# STM32.net
KiCad netlist of a schematic drawn in Altium Designer
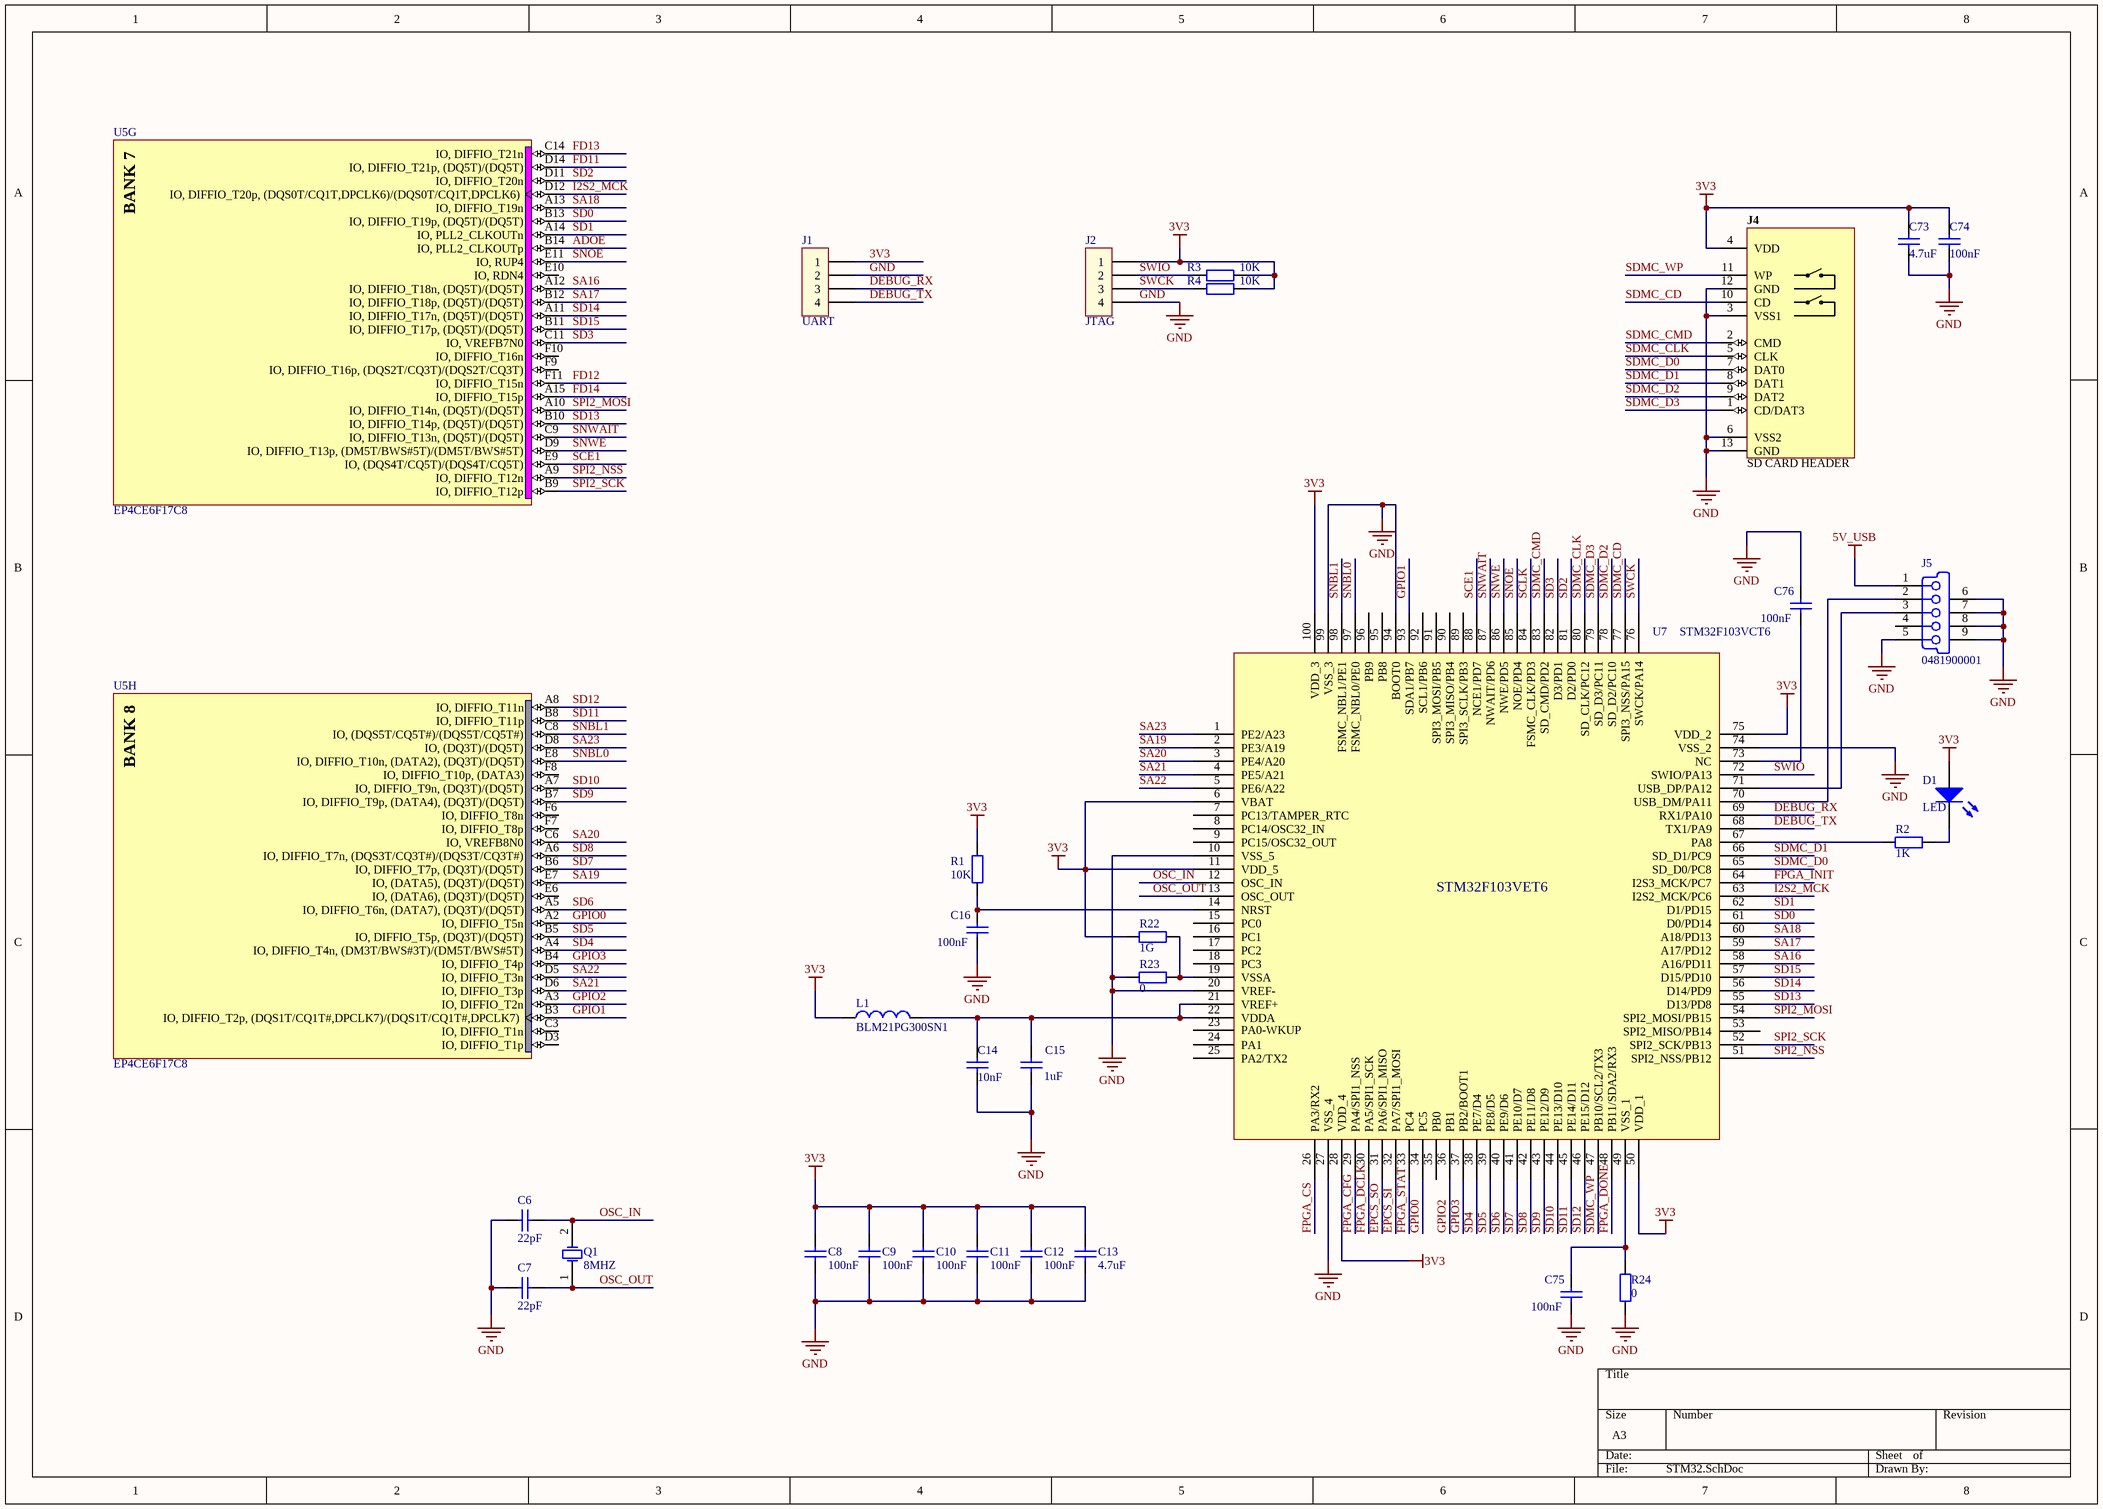
[diagram p0: STM32.SchDoc]

(export (version "E")
  (design (tool "Eeschema 10.0.6"))
  (components
    (comp (ref "C6")
      (value "22pF")
      (footprint "C0603")
      (description "Capacitor")
      (fields (field (name "PUBLISHER") "Altium Limited"))
      (libsource (lib "Miscellaneous Devices") (part "Cap"))
    )
    (comp (ref "C7")
      (value "22pF")
      (footprint "C0603")
      (description "Capacitor")
      (fields (field (name "PUBLISHER") "Altium Limited"))
      (libsource (lib "Miscellaneous Devices") (part "Cap"))
    )
    (comp (ref "C8")
      (value "100nF")
      (footprint "C0603")
      (description "Capacitor")
      (fields (field (name "PUBLISHER") "Altium Limited"))
      (libsource (lib "Miscellaneous Devices") (part "Cap"))
    )
    (comp (ref "C9")
      (value "100nF")
      (footprint "C0603")
      (description "Capacitor")
      (fields (field (name "PUBLISHER") "Altium Limited"))
      (libsource (lib "Miscellaneous Devices") (part "Cap"))
    )
    (comp (ref "C10")
      (value "100nF")
      (footprint "C0603")
      (description "Capacitor")
      (fields (field (name "PUBLISHER") "Altium Limited"))
      (libsource (lib "Miscellaneous Devices") (part "Cap"))
    )
    (comp (ref "C11")
      (value "100nF")
      (footprint "C0603")
      (description "Capacitor")
      (fields (field (name "PUBLISHER") "Altium Limited"))
      (libsource (lib "Miscellaneous Devices") (part "Cap"))
    )
    (comp (ref "C12")
      (value "100nF")
      (footprint "C0603")
      (description "Capacitor")
      (fields (field (name "PUBLISHER") "Altium Limited"))
      (libsource (lib "Miscellaneous Devices") (part "Cap"))
    )
    (comp (ref "C13")
      (value "4.7uF")
      (footprint "C0603")
      (description "Capacitor")
      (fields (field (name "PUBLISHER") "Altium Limited"))
      (libsource (lib "Miscellaneous Devices") (part "Cap"))
    )
    (comp (ref "C14")
      (value "10nF")
      (footprint "C0603")
      (description "Capacitor")
      (fields (field (name "PUBLISHER") "Altium Limited"))
      (libsource (lib "Miscellaneous Devices") (part "Cap"))
    )
    (comp (ref "C15")
      (value "1uF")
      (footprint "C0603")
      (description "Capacitor")
      (fields (field (name "PUBLISHER") "Altium Limited"))
      (libsource (lib "Miscellaneous Devices") (part "Cap"))
    )
    (comp (ref "C16")
      (value "100nF")
      (footprint "C0603")
      (description "Capacitor")
      (fields (field (name "PUBLISHER") "Altium Limited"))
      (libsource (lib "Miscellaneous Devices") (part "Cap"))
    )
    (comp (ref "C73")
      (value "4.7uF")
      (footprint "C0603")
      (description "Capacitor")
      (fields (field (name "PUBLISHER") "Altium Limited"))
      (libsource (lib "Miscellaneous Devices") (part "Cap"))
    )
    (comp (ref "C74")
      (value "100nF")
      (footprint "C0603")
      (description "Capacitor")
      (fields (field (name "PUBLISHER") "Altium Limited"))
      (libsource (lib "Miscellaneous Devices") (part "Cap"))
    )
    (comp (ref "C75")
      (value "100nF")
      (footprint "C0603")
      (description "Capacitor")
      (fields (field (name "PUBLISHER") "Altium Limited"))
      (libsource (lib "Miscellaneous Devices") (part "Cap"))
    )
    (comp (ref "C76")
      (value "100nF")
      (footprint "C0603")
      (description "Capacitor")
      (fields (field (name "PUBLISHER") "Altium Limited"))
      (libsource (lib "Miscellaneous Devices") (part "Cap"))
    )
    (comp (ref "D1")
      (value "LED")
      (footprint "D0603")
      (description "Typical RED GaAs LED")
      (fields (field (name "PUBLISHER") "Altium Limited"))
      (libsource (lib "PCB_Project1") (part "LED1"))
    )
    (comp (ref "J1") (value "UART") (footprint "SIP4") (libsource (lib "Schlib1") (part "SIP4")))
    (comp (ref "J2") (value "JTAG") (footprint "SIP4") (libsource (lib "Schlib1") (part "SIP4")))
    (comp (ref "J4")
      (value "SD CARD HEADER")
      (footprint "KSDC012551")
      (description "Secure Digital Card Socket")
      (libsource (lib "ssmaster_1") (part "KSDC012551-9"))
    )
    (comp (ref "J5")
      (value "0481900001")
      (footprint "ssmaster_1:Micro USB")
      (fields (field (name "PUBLISHER") "Altium Limited"))
      (libsource (lib "Molex Serial Bus Mini USB") (part "0481900001"))
    )
    (comp (ref "L1")
      (value "BLM21PG300SN1")
      (footprint "R0805")
      (description "Inductor")
      (fields (field (name "PUBLISHER") "Altium Limited"))
      (libsource (lib "Miscellaneous Devices") (part "Inductor"))
    )
    (comp (ref "Q1")
      (value "8MHZ")
      (footprint "SMD_CRYSTAL")
      (description "Crystal Oscillator")
      (fields (field (name "PUBLISHER") "Altium Limited"))
      (libsource (lib "Miscellaneous Devices") (part "XTAL"))
    )
    (comp (ref "R1")
      (value "10K")
      (footprint "R0603")
      (description "Resistor")
      (fields (field (name "PUBLISHER") "Altium Limited"))
      (libsource (lib "Miscellaneous Devices") (part "Res2"))
    )
    (comp (ref "R2")
      (value "1K")
      (footprint "R0603")
      (description "Resistor")
      (fields (field (name "PUBLISHER") "Altium Limited"))
      (libsource (lib "") (part "Res2_2"))
    )
    (comp (ref "R3")
      (value "10K")
      (footprint "R0603")
      (description "Resistor")
      (fields (field (name "PUBLISHER") "Altium Limited"))
      (libsource (lib "") (part "Res2_3"))
    )
    (comp (ref "R4")
      (value "10K")
      (footprint "R0603")
      (description "Resistor")
      (fields (field (name "PUBLISHER") "Altium Limited"))
      (libsource (lib "") (part "Res2_3"))
    )
    (comp (ref "R22")
      (value "1G")
      (footprint "R0603")
      (description "Resistor")
      (fields (field (name "PUBLISHER") "Altium Limited"))
      (libsource (lib "") (part "Res2_2"))
    )
    (comp (ref "R23")
      (value "0")
      (footprint "R0603")
      (description "Resistor")
      (fields (field (name "PUBLISHER") "Altium Limited"))
      (libsource (lib "") (part "Res2_2"))
    )
    (comp (ref "R24")
      (value "0")
      (footprint "R0603")
      (description "Resistor")
      (fields (field (name "PUBLISHER") "Altium Limited"))
      (libsource (lib "") (part "Res2_1"))
    )
    (comp (ref "U5")
      (value "EP4CE6F17C8")
      (footprint "FBGA256")
      (fields (field (name "PUBLISHER") "Altium Limited"))
      (libsource (lib "Altera Cyclone IV E") (part "EP4CE6F17C8"))
    )
    (comp (ref "U7")
      (value "STM32F103VCT6")
      (footprint "TQFP-100")
      (libsource (lib "ssmaster_1") (part "STM32F103VCT6"))
    )
  )
  (nets
    (net (code "1") (name "/ADOE") (class "Default")
      (node (ref "U5") (pin "B14") (pinfunction "IO,_PLL2_CLKOUTp_B14") (pintype "bidirectional"))
    )
    (net (code "2") (name "/DEBUG_RX") (class "Default")
      (node (ref "J1") (pin "3") (pinfunction "3_3") (pintype "passive"))
      (node (ref "U7") (pin "69") (pinfunction "RX1/PA10_69") (pintype "passive"))
    )
    (net (code "3") (name "/DEBUG_TX") (class "Default")
      (node (ref "J1") (pin "4") (pinfunction "4_4") (pintype "passive"))
      (node (ref "U7") (pin "68") (pinfunction "TX1/PA9_68") (pintype "passive"))
    )
    (net (code "4") (name "/EPCS_SI") (class "Default")
      (node (ref "U7") (pin "32") (pinfunction "PA7/SPI1_MOSI_32") (pintype "passive"))
    )
    (net (code "5") (name "/EPCS_SO") (class "Default")
      (node (ref "U7") (pin "31") (pinfunction "PA6/SPI1_MISO_31") (pintype "passive"))
    )
    (net (code "6") (name "/FD11") (class "Default")
      (node (ref "U5") (pin "D14") (pinfunction "IO,_DIFFIO_T21p,_(DQ5T)/(DQ5T)_D14") (pintype "bidirectional"))
    )
    (net (code "7") (name "/FD12") (class "Default")
      (node (ref "U5") (pin "F11") (pinfunction "IO,_DIFFIO_T15n_F11") (pintype "bidirectional"))
    )
    (net (code "8") (name "/FD13") (class "Default")
      (node (ref "U5") (pin "C14") (pinfunction "IO,_DIFFIO_T21n_C14") (pintype "bidirectional"))
    )
    (net (code "9") (name "/FD14") (class "Default")
      (node (ref "U5") (pin "A15") (pinfunction "IO,_DIFFIO_T15p_A15") (pintype "bidirectional"))
    )
    (net (code "10") (name "/FPGA_CFG") (class "Default")
      (node (ref "U7") (pin "29") (pinfunction "PA4/SPI1_NSS_29") (pintype "passive"))
    )
    (net (code "11") (name "/FPGA_CS") (class "Default")
      (node (ref "U7") (pin "26") (pinfunction "PA3/RX2_26") (pintype "passive"))
    )
    (net (code "12") (name "/FPGA_DCLK") (class "Default")
      (node (ref "U7") (pin "30") (pinfunction "PA5/SPI1_SCK_30") (pintype "passive"))
    )
    (net (code "13") (name "/FPGA_DONE") (class "Default")
      (node (ref "U7") (pin "48") (pinfunction "PB11/SDA2/RX3_48") (pintype "passive"))
    )
    (net (code "14") (name "/FPGA_INIT") (class "Default")
      (node (ref "U7") (pin "64") (pinfunction "I2S3_MCK/PC7_64") (pintype "passive"))
    )
    (net (code "15") (name "/FPGA_STAT") (class "Default")
      (node (ref "U7") (pin "33") (pinfunction "PC4_33") (pintype "passive"))
    )
    (net (code "16") (name "/GPIO0") (class "Default")
      (node (ref "U5") (pin "A2") (pinfunction "IO,_DIFFIO_T5n_A2") (pintype "bidirectional"))
      (node (ref "U7") (pin "34") (pinfunction "PC5_34") (pintype "passive"))
    )
    (net (code "17") (name "/GPIO1") (class "Default")
      (node (ref "U5") (pin "B3") (pinfunction "IO,_DIFFIO_T2p,_(DQS1T/CQ1T#,DPCLK7)/(DQS1T/CQ1T#,DPCLK7)_B3") (pintype "bidirectional"))
      (node (ref "U7") (pin "93") (pinfunction "SDA1/PB7_93") (pintype "passive"))
    )
    (net (code "18") (name "/GPIO2") (class "Default")
      (node (ref "U5") (pin "A3") (pinfunction "IO,_DIFFIO_T2n_A3") (pintype "bidirectional"))
      (node (ref "U7") (pin "36") (pinfunction "PB1_36") (pintype "passive"))
    )
    (net (code "19") (name "/GPIO3") (class "Default")
      (node (ref "U5") (pin "B4") (pinfunction "IO,_DIFFIO_T4p_B4") (pintype "bidirectional"))
      (node (ref "U7") (pin "37") (pinfunction "PB2/BOOT1_37") (pintype "passive"))
    )
    (net (code "20") (name "/I2S2_MCK") (class "Default")
      (node (ref "U5") (pin "D12") (pinfunction "IO,_DIFFIO_T20p,_(DQS0T/CQ1T,DPCLK6)/(DQS0T/CQ1T,DPCLK6)_D12") (pintype "bidirectional"))
      (node (ref "U7") (pin "63") (pinfunction "I2S2_MCK/PC6_63") (pintype "passive"))
    )
    (net (code "21") (name "/OSC_IN") (class "Default")
      (node (ref "C6") (pin "1") (pinfunction "1_1") (pintype "passive"))
      (node (ref "Q1") (pin "2") (pinfunction "OSC2_2") (pintype "passive"))
      (node (ref "U7") (pin "12") (pinfunction "OSC_IN_12") (pintype "passive"))
    )
    (net (code "22") (name "/OSC_OUT") (class "Default")
      (node (ref "C7") (pin "1") (pinfunction "1_1") (pintype "passive"))
      (node (ref "Q1") (pin "1") (pinfunction "OSC1_1") (pintype "passive"))
      (node (ref "U7") (pin "13") (pinfunction "OSC_OUT_13") (pintype "passive"))
    )
    (net (code "23") (name "/SA16") (class "Default")
      (node (ref "U5") (pin "A12") (pinfunction "IO,_DIFFIO_T18n,_(DQ5T)/(DQ5T)_A12") (pintype "bidirectional"))
      (node (ref "U7") (pin "58") (pinfunction "A16/PD11_58") (pintype "passive"))
    )
    (net (code "24") (name "/SA17") (class "Default")
      (node (ref "U5") (pin "B12") (pinfunction "IO,_DIFFIO_T18p,_(DQ5T)/(DQ5T)_B12") (pintype "bidirectional"))
      (node (ref "U7") (pin "59") (pinfunction "A17/PD12_59") (pintype "passive"))
    )
    (net (code "25") (name "/SA18") (class "Default")
      (node (ref "U5") (pin "A13") (pinfunction "IO,_DIFFIO_T19n_A13") (pintype "bidirectional"))
      (node (ref "U7") (pin "60") (pinfunction "A18/PD13_60") (pintype "passive"))
    )
    (net (code "26") (name "/SA19") (class "Default")
      (node (ref "U5") (pin "E7") (pinfunction "IO,_(DATA5),_(DQ3T)/(DQ5T)_E7") (pintype "bidirectional"))
      (node (ref "U7") (pin "2") (pinfunction "PE3/A19_2") (pintype "passive"))
    )
    (net (code "27") (name "/SA20") (class "Default")
      (node (ref "U5") (pin "C6") (pinfunction "IO,_VREFB8N0_C6") (pintype "bidirectional"))
      (node (ref "U7") (pin "3") (pinfunction "PE4/A20_3") (pintype "passive"))
    )
    (net (code "28") (name "/SA21") (class "Default")
      (node (ref "U5") (pin "D6") (pinfunction "IO,_DIFFIO_T3p_D6") (pintype "bidirectional"))
      (node (ref "U7") (pin "4") (pinfunction "PE5/A21_4") (pintype "passive"))
    )
    (net (code "29") (name "/SA22") (class "Default")
      (node (ref "U5") (pin "D5") (pinfunction "IO,_DIFFIO_T3n_D5") (pintype "bidirectional"))
      (node (ref "U7") (pin "5") (pinfunction "PE6/A22_5") (pintype "passive"))
    )
    (net (code "30") (name "/SA23") (class "Default")
      (node (ref "U5") (pin "D8") (pinfunction "IO,_(DQ3T)/(DQ5T)_D8") (pintype "bidirectional"))
      (node (ref "U7") (pin "1") (pinfunction "PE2/A23_1") (pintype "passive"))
    )
    (net (code "31") (name "/SCE1") (class "Default")
      (node (ref "U5") (pin "E9") (pinfunction "IO,_(DQS4T/CQ5T)/(DQS4T/CQ5T)_E9") (pintype "bidirectional"))
      (node (ref "U7") (pin "88") (pinfunction "NCE1/PD7_88") (pintype "passive"))
    )
    (net (code "32") (name "/SCLK") (class "Default")
      (node (ref "U7") (pin "84") (pinfunction "FSMC_CLK/PD3_84") (pintype "passive"))
    )
    (net (code "33") (name "/SD0") (class "Default")
      (node (ref "U5") (pin "B13") (pinfunction "IO,_DIFFIO_T19p,_(DQ5T)/(DQ5T)_B13") (pintype "bidirectional"))
      (node (ref "U7") (pin "61") (pinfunction "D0/PD14_61") (pintype "passive"))
    )
    (net (code "34") (name "/SD1") (class "Default")
      (node (ref "U5") (pin "A14") (pinfunction "IO,_PLL2_CLKOUTn_A14") (pintype "bidirectional"))
      (node (ref "U7") (pin "62") (pinfunction "D1/PD15_62") (pintype "passive"))
    )
    (net (code "35") (name "/SD2") (class "Default")
      (node (ref "U5") (pin "D11") (pinfunction "IO,_DIFFIO_T20n_D11") (pintype "bidirectional"))
      (node (ref "U7") (pin "81") (pinfunction "D2/PD0_81") (pintype "passive"))
    )
    (net (code "36") (name "/SD3") (class "Default")
      (node (ref "U5") (pin "C11") (pinfunction "IO,_VREFB7N0_C11") (pintype "bidirectional"))
      (node (ref "U7") (pin "82") (pinfunction "D3/PD1_82") (pintype "passive"))
    )
    (net (code "37") (name "/SD4") (class "Default")
      (node (ref "U5") (pin "A4") (pinfunction "IO,_DIFFIO_T4n,_(DM3T/BWS#3T)/(DM5T/BWS#5T)_A4") (pintype "bidirectional"))
      (node (ref "U7") (pin "38") (pinfunction "PE7/D4_38") (pintype "passive"))
    )
    (net (code "38") (name "/SD5") (class "Default")
      (node (ref "U5") (pin "B5") (pinfunction "IO,_DIFFIO_T5p,_(DQ3T)/(DQ5T)_B5") (pintype "bidirectional"))
      (node (ref "U7") (pin "39") (pinfunction "PE8/D5_39") (pintype "passive"))
    )
    (net (code "39") (name "/SD6") (class "Default")
      (node (ref "U5") (pin "A5") (pinfunction "IO,_DIFFIO_T6n,_(DATA7),_(DQ3T)/(DQ5T)_A5") (pintype "bidirectional"))
      (node (ref "U7") (pin "40") (pinfunction "PE9/D6_40") (pintype "passive"))
    )
    (net (code "40") (name "/SD7") (class "Default")
      (node (ref "U5") (pin "B6") (pinfunction "IO,_DIFFIO_T7p,_(DQ3T)/(DQ5T)_B6") (pintype "bidirectional"))
      (node (ref "U7") (pin "41") (pinfunction "PE10/D7_41") (pintype "passive"))
    )
    (net (code "41") (name "/SD8") (class "Default")
      (node (ref "U5") (pin "A6") (pinfunction "IO,_DIFFIO_T7n,_(DQS3T/CQ3T#)/(DQS3T/CQ3T#)_A6") (pintype "bidirectional"))
      (node (ref "U7") (pin "42") (pinfunction "PE11/D8_42") (pintype "passive"))
    )
    (net (code "42") (name "/SD9") (class "Default")
      (node (ref "U5") (pin "B7") (pinfunction "IO,_DIFFIO_T9p,_(DATA4),_(DQ3T)/(DQ5T)_B7") (pintype "bidirectional"))
      (node (ref "U7") (pin "43") (pinfunction "PE12/D9_43") (pintype "passive"))
    )
    (net (code "43") (name "/SD10") (class "Default")
      (node (ref "U5") (pin "A7") (pinfunction "IO,_DIFFIO_T9n,_(DQ3T)/(DQ5T)_A7") (pintype "bidirectional"))
      (node (ref "U7") (pin "44") (pinfunction "PE13/D10_44") (pintype "passive"))
    )
    (net (code "44") (name "/SD11") (class "Default")
      (node (ref "U5") (pin "B8") (pinfunction "IO,_DIFFIO_T11p_B8") (pintype "bidirectional"))
      (node (ref "U7") (pin "45") (pinfunction "PE14/D11_45") (pintype "passive"))
    )
    (net (code "45") (name "/SD12") (class "Default")
      (node (ref "U5") (pin "A8") (pinfunction "IO,_DIFFIO_T11n_A8") (pintype "bidirectional"))
      (node (ref "U7") (pin "46") (pinfunction "PE15/D12_46") (pintype "passive"))
    )
    (net (code "46") (name "/SD13") (class "Default")
      (node (ref "U5") (pin "B10") (pinfunction "IO,_DIFFIO_T14p,_(DQ5T)/(DQ5T)_B10") (pintype "bidirectional"))
      (node (ref "U7") (pin "55") (pinfunction "D13/PD8_55") (pintype "passive"))
    )
    (net (code "47") (name "/SD14") (class "Default")
      (node (ref "U5") (pin "A11") (pinfunction "IO,_DIFFIO_T17n,_(DQ5T)/(DQ5T)_A11") (pintype "bidirectional"))
      (node (ref "U7") (pin "56") (pinfunction "D14/PD9_56") (pintype "passive"))
    )
    (net (code "48") (name "/SD15") (class "Default")
      (node (ref "U5") (pin "B11") (pinfunction "IO,_DIFFIO_T17p,_(DQ5T)/(DQ5T)_B11") (pintype "bidirectional"))
      (node (ref "U7") (pin "57") (pinfunction "D15/PD10_57") (pintype "passive"))
    )
    (net (code "49") (name "/SDMC_CD") (class "Default")
      (node (ref "J4") (pin "10") (pinfunction "CD_10") (pintype "open_collector"))
      (node (ref "U7") (pin "77") (pinfunction "SPI3_NSS/PA15_77") (pintype "passive"))
    )
    (net (code "50") (name "/SDMC_CLK") (class "Default")
      (node (ref "J4") (pin "5") (pinfunction "CLK_5") (pintype "bidirectional"))
      (node (ref "U7") (pin "80") (pinfunction "SD_CLK/PC12_80") (pintype "passive"))
    )
    (net (code "51") (name "/SDMC_CMD") (class "Default")
      (node (ref "J4") (pin "2") (pinfunction "CMD_2") (pintype "bidirectional"))
      (node (ref "U7") (pin "83") (pinfunction "SD_CMD/PD2_83") (pintype "passive"))
    )
    (net (code "52") (name "/SDMC_D0") (class "Default")
      (node (ref "J4") (pin "7") (pinfunction "DAT0_7") (pintype "bidirectional"))
      (node (ref "U7") (pin "65") (pinfunction "SD_D0/PC8_65") (pintype "passive"))
    )
    (net (code "53") (name "/SDMC_D1") (class "Default")
      (node (ref "J4") (pin "8") (pinfunction "DAT1_8") (pintype "bidirectional"))
      (node (ref "U7") (pin "66") (pinfunction "SD_D1/PC9_66") (pintype "passive"))
    )
    (net (code "54") (name "/SDMC_D2") (class "Default")
      (node (ref "J4") (pin "9") (pinfunction "DAT2_9") (pintype "bidirectional"))
      (node (ref "U7") (pin "78") (pinfunction "SD_D2/PC10_78") (pintype "passive"))
    )
    (net (code "55") (name "/SDMC_D3") (class "Default")
      (node (ref "J4") (pin "1") (pinfunction "CD/DAT3_1") (pintype "bidirectional"))
      (node (ref "U7") (pin "79") (pinfunction "SD_D3/PC11_79") (pintype "passive"))
    )
    (net (code "56") (name "/SDMC_WP") (class "Default")
      (node (ref "J4") (pin "11") (pinfunction "WP_11") (pintype "open_collector"))
      (node (ref "U7") (pin "47") (pinfunction "PB10/SCL2/TX3_47") (pintype "passive"))
    )
    (net (code "57") (name "/SNBL0") (class "Default")
      (node (ref "U5") (pin "E8") (pinfunction "IO,_DIFFIO_T10n,_(DATA2),_(DQ3T)/(DQ5T)_E8") (pintype "bidirectional"))
      (node (ref "U7") (pin "97") (pinfunction "FSMC_NBL0/PE0_97") (pintype "passive"))
    )
    (net (code "58") (name "/SNBL1") (class "Default")
      (node (ref "U5") (pin "C8") (pinfunction "IO,_(DQS5T/CQ5T#)/(DQS5T/CQ5T#)_C8") (pintype "bidirectional"))
      (node (ref "U7") (pin "98") (pinfunction "FSMC_NBL1/PE1_98") (pintype "passive"))
    )
    (net (code "59") (name "/SNOE") (class "Default")
      (node (ref "U5") (pin "E11") (pinfunction "IO,_RUP4_E11") (pintype "bidirectional"))
      (node (ref "U7") (pin "85") (pinfunction "NOE/PD4_85") (pintype "passive"))
    )
    (net (code "60") (name "/SNWAIT") (class "Default")
      (node (ref "U5") (pin "C9") (pinfunction "IO,_DIFFIO_T13n,_(DQ5T)/(DQ5T)_C9") (pintype "bidirectional"))
      (node (ref "U7") (pin "87") (pinfunction "NWAIT/PD6_87") (pintype "passive"))
    )
    (net (code "61") (name "/SNWE") (class "Default")
      (node (ref "U5") (pin "D9") (pinfunction "IO,_DIFFIO_T13p,_(DM5T/BWS#5T)/(DM5T/BWS#5T)_D9") (pintype "bidirectional"))
      (node (ref "U7") (pin "86") (pinfunction "NWE/PD5_86") (pintype "passive"))
    )
    (net (code "62") (name "/SPI2_MOSI") (class "Default")
      (node (ref "U5") (pin "A10") (pinfunction "IO,_DIFFIO_T14n,_(DQ5T)/(DQ5T)_A10") (pintype "bidirectional"))
      (node (ref "U7") (pin "54") (pinfunction "SPI2_MOSI/PB15_54") (pintype "passive"))
    )
    (net (code "63") (name "/SPI2_NSS") (class "Default")
      (node (ref "U5") (pin "A9") (pinfunction "IO,_DIFFIO_T12n_A9") (pintype "bidirectional"))
      (node (ref "U7") (pin "51") (pinfunction "SPI2_NSS/PB12_51") (pintype "passive"))
    )
    (net (code "64") (name "/SPI2_SCK") (class "Default")
      (node (ref "U5") (pin "B9") (pinfunction "IO,_DIFFIO_T12p_B9") (pintype "bidirectional"))
      (node (ref "U7") (pin "52") (pinfunction "SPI2_SCK/PB13_52") (pintype "passive"))
    )
    (net (code "65") (name "/SWCK") (class "Default")
      (node (ref "J2") (pin "3") (pinfunction "3_3") (pintype "passive"))
      (node (ref "R4") (pin "1") (pinfunction "1_1") (pintype "passive"))
      (node (ref "U7") (pin "76") (pinfunction "SWCK/PA14_76") (pintype "passive"))
    )
    (net (code "66") (name "/SWIO") (class "Default")
      (node (ref "J2") (pin "2") (pinfunction "2_2") (pintype "passive"))
      (node (ref "R3") (pin "1") (pinfunction "1_1") (pintype "passive"))
      (node (ref "U7") (pin "72") (pinfunction "SWIO/PA13_72") (pintype "passive"))
    )
    (net (code "67") (name "3V3") (class "Default")
      (node (ref "C10") (pin "2") (pinfunction "2_2") (pintype "passive"))
      (node (ref "C11") (pin "2") (pinfunction "2_2") (pintype "passive"))
      (node (ref "C12") (pin "2") (pinfunction "2_2") (pintype "passive"))
      (node (ref "C13") (pin "2") (pinfunction "2_2") (pintype "passive"))
      (node (ref "C73") (pin "2") (pinfunction "2_2") (pintype "passive"))
      (node (ref "C74") (pin "2") (pinfunction "2_2") (pintype "passive"))
      (node (ref "C8") (pin "2") (pinfunction "2_2") (pintype "passive"))
      (node (ref "C9") (pin "2") (pinfunction "2_2") (pintype "passive"))
      (node (ref "D1") (pin "1") (pinfunction "1_1") (pintype "passive"))
      (node (ref "J1") (pin "1") (pinfunction "1_1") (pintype "passive"))
      (node (ref "J2") (pin "1") (pinfunction "1_1") (pintype "passive"))
      (node (ref "J4") (pin "4") (pinfunction "VDD_4") (pintype "power_in"))
      (node (ref "L1") (pin "1") (pinfunction "1_1") (pintype "passive"))
      (node (ref "R1") (pin "2") (pinfunction "2_2") (pintype "passive"))
      (node (ref "R22") (pin "2") (pinfunction "2_2") (pintype "passive"))
      (node (ref "R3") (pin "2") (pinfunction "2_2") (pintype "passive"))
      (node (ref "R4") (pin "2") (pinfunction "2_2") (pintype "passive"))
      (node (ref "U7") (pin "100") (pinfunction "VDD_3_100") (pintype "passive"))
      (node (ref "U7") (pin "11") (pinfunction "VDD_5_11") (pintype "passive"))
      (node (ref "U7") (pin "28") (pinfunction "VDD_4_28") (pintype "passive"))
      (node (ref "U7") (pin "50") (pinfunction "VDD_1_50") (pintype "passive"))
      (node (ref "U7") (pin "6") (pinfunction "VBAT_6") (pintype "passive"))
      (node (ref "U7") (pin "75") (pinfunction "VDD_2_75") (pintype "passive"))
    )
    (net (code "68") (name "5V_USB") (class "Default")
      (node (ref "J5") (pin "1") (pinfunction "V_BUS_(5V)_1") (pintype "passive"))
    )
    (net (code "69") (name "GND") (class "Default")
      (node (ref "C10") (pin "1") (pinfunction "1_1") (pintype "passive"))
      (node (ref "C11") (pin "1") (pinfunction "1_1") (pintype "passive"))
      (node (ref "C12") (pin "1") (pinfunction "1_1") (pintype "passive"))
      (node (ref "C13") (pin "1") (pinfunction "1_1") (pintype "passive"))
      (node (ref "C14") (pin "1") (pinfunction "1_1") (pintype "passive"))
      (node (ref "C15") (pin "1") (pinfunction "1_1") (pintype "passive"))
      (node (ref "C16") (pin "2") (pinfunction "2_2") (pintype "passive"))
      (node (ref "C6") (pin "2") (pinfunction "2_2") (pintype "passive"))
      (node (ref "C7") (pin "2") (pinfunction "2_2") (pintype "passive"))
      (node (ref "C73") (pin "1") (pinfunction "1_1") (pintype "passive"))
      (node (ref "C74") (pin "1") (pinfunction "1_1") (pintype "passive"))
      (node (ref "C75") (pin "2") (pinfunction "2_2") (pintype "passive"))
      (node (ref "C76") (pin "1") (pinfunction "1_1") (pintype "passive"))
      (node (ref "C8") (pin "1") (pinfunction "1_1") (pintype "passive"))
      (node (ref "C9") (pin "1") (pinfunction "1_1") (pintype "passive"))
      (node (ref "J1") (pin "2") (pinfunction "2_2") (pintype "passive"))
      (node (ref "J2") (pin "4") (pinfunction "4_4") (pintype "passive"))
      (node (ref "J4") (pin "12") (pinfunction "GND_12") (pintype "power_in"))
      (node (ref "J4") (pin "13") (pinfunction "GND_13") (pintype "power_in"))
      (node (ref "J4") (pin "3") (pinfunction "VSS1_3") (pintype "power_in"))
      (node (ref "J4") (pin "6") (pinfunction "VSS2_6") (pintype "power_in"))
      (node (ref "J5") (pin "5") (pinfunction "GND_5") (pintype "passive"))
      (node (ref "J5") (pin "6") (pinfunction "Tab_6") (pintype "passive"))
      (node (ref "J5") (pin "7") (pinfunction "Tab_7") (pintype "passive"))
      (node (ref "J5") (pin "8") (pinfunction "Tab_8") (pintype "passive"))
      (node (ref "J5") (pin "9") (pinfunction "Tab_9") (pintype "passive"))
      (node (ref "R23") (pin "2") (pinfunction "2_2") (pintype "passive"))
      (node (ref "R24") (pin "2") (pinfunction "2_2") (pintype "passive"))
      (node (ref "U7") (pin "10") (pinfunction "VSS_5_10") (pintype "passive"))
      (node (ref "U7") (pin "20") (pinfunction "VREF-_20") (pintype "passive"))
      (node (ref "U7") (pin "27") (pinfunction "VSS_4_27") (pintype "passive"))
      (node (ref "U7") (pin "74") (pinfunction "VSS_2_74") (pintype "passive"))
      (node (ref "U7") (pin "94") (pinfunction "BOOT0_94") (pintype "passive"))
      (node (ref "U7") (pin "99") (pinfunction "VSS_3_99") (pintype "passive"))
    )
    (net (code "70") (name "Net-(D1-Pad2)") (class "Default")
      (node (ref "D1") (pin "2") (pinfunction "2_2") (pintype "passive"))
      (node (ref "R2") (pin "1") (pinfunction "1_1") (pintype "passive"))
    )
    (net (code "71") (name "Net-(J5-D+)") (class "Default")
      (node (ref "J5") (pin "3") (pinfunction "D+_3") (pintype "passive"))
      (node (ref "U7") (pin "71") (pinfunction "USB_DP/PA12_71") (pintype "passive"))
    )
    (net (code "72") (name "Net-(J5-D-)") (class "Default")
      (node (ref "J5") (pin "2") (pinfunction "D-_2") (pintype "passive"))
      (node (ref "U7") (pin "70") (pinfunction "USB_DM/PA11_70") (pintype "passive"))
    )
    (net (code "73") (name "Net-(U7-NC)") (class "Default")
      (node (ref "C76") (pin "2") (pinfunction "2_2") (pintype "passive"))
      (node (ref "U7") (pin "73") (pinfunction "NC_73") (pintype "passive"))
    )
    (net (code "74") (name "Net-(U7-NRST)") (class "Default")
      (node (ref "C16") (pin "1") (pinfunction "1_1") (pintype "passive"))
      (node (ref "R1") (pin "1") (pinfunction "1_1") (pintype "passive"))
      (node (ref "U7") (pin "14") (pinfunction "NRST_14") (pintype "passive"))
    )
    (net (code "75") (name "Net-(U7-PA8)") (class "Default")
      (node (ref "R2") (pin "2") (pinfunction "2_2") (pintype "passive"))
      (node (ref "U7") (pin "67") (pinfunction "PA8_67") (pintype "passive"))
    )
    (net (code "76") (name "Net-(U7-VDDA)") (class "Default")
      (node (ref "C14") (pin "2") (pinfunction "2_2") (pintype "passive"))
      (node (ref "C15") (pin "2") (pinfunction "2_2") (pintype "passive"))
      (node (ref "L1") (pin "2") (pinfunction "2_2") (pintype "passive"))
      (node (ref "U7") (pin "21") (pinfunction "VREF+_21") (pintype "passive"))
      (node (ref "U7") (pin "22") (pinfunction "VDDA_22") (pintype "passive"))
    )
    (net (code "77") (name "Net-(U7-VSSA)") (class "Default")
      (node (ref "R22") (pin "1") (pinfunction "1_1") (pintype "passive"))
      (node (ref "R23") (pin "1") (pinfunction "1_1") (pintype "passive"))
      (node (ref "U7") (pin "19") (pinfunction "VSSA_19") (pintype "passive"))
    )
    (net (code "78") (name "Net-(U7-VSS_1)") (class "Default")
      (node (ref "C75") (pin "1") (pinfunction "1_1") (pintype "passive"))
      (node (ref "R24") (pin "1") (pinfunction "1_1") (pintype "passive"))
      (node (ref "U7") (pin "49") (pinfunction "VSS_1_49") (pintype "passive"))
    )
    (net (code "79") (name "unconnected-(J5-NC-Pad4)") (class "Default")
      (node (ref "J5") (pin "4") (pinfunction "NC_4") (pintype "passive"))
    )
    (net (code "80") (name "unconnected-(U5G-IO,_DIFFIO_T16n-PadF10)") (class "Default")
      (node (ref "U5") (pin "F10") (pinfunction "IO,_DIFFIO_T16n_F10") (pintype "bidirectional"))
    )
    (net (code "81") (name "unconnected-(U5G-IO,_DIFFIO_T16p,_(DQS2T{slash}CQ3T){slash}(DQS2T{slash}CQ3T)-PadF9)") (class "Default")
      (node (ref "U5") (pin "F9") (pinfunction "IO,_DIFFIO_T16p,_(DQS2T/CQ3T)/(DQS2T/CQ3T)_F9") (pintype "bidirectional"))
    )
    (net (code "82") (name "unconnected-(U5G-IO,_RDN4-PadE10)") (class "Default")
      (node (ref "U5") (pin "E10") (pinfunction "IO,_RDN4_E10") (pintype "bidirectional"))
    )
    (net (code "83") (name "unconnected-(U5H-IO,_(DATA6),_(DQ3T){slash}(DQ5T)-PadE6)") (class "Default")
      (node (ref "U5") (pin "E6") (pinfunction "IO,_(DATA6),_(DQ3T)/(DQ5T)_E6") (pintype "bidirectional"))
    )
    (net (code "84") (name "unconnected-(U5H-IO,_DIFFIO_T1n-PadC3)") (class "Default")
      (node (ref "U5") (pin "C3") (pinfunction "IO,_DIFFIO_T1n_C3") (pintype "bidirectional"))
    )
    (net (code "85") (name "unconnected-(U5H-IO,_DIFFIO_T1p-PadD3)") (class "Default")
      (node (ref "U5") (pin "D3") (pinfunction "IO,_DIFFIO_T1p_D3") (pintype "bidirectional"))
    )
    (net (code "86") (name "unconnected-(U5H-IO,_DIFFIO_T8n-PadF6)") (class "Default")
      (node (ref "U5") (pin "F6") (pinfunction "IO,_DIFFIO_T8n_F6") (pintype "bidirectional"))
    )
    (net (code "87") (name "unconnected-(U5H-IO,_DIFFIO_T8p-PadF7)") (class "Default")
      (node (ref "U5") (pin "F7") (pinfunction "IO,_DIFFIO_T8p_F7") (pintype "bidirectional"))
    )
    (net (code "88") (name "unconnected-(U5H-IO,_DIFFIO_T10p,_(DATA3)-PadF8)") (class "Default")
      (node (ref "U5") (pin "F8") (pinfunction "IO,_DIFFIO_T10p,_(DATA3)_F8") (pintype "bidirectional"))
    )
    (net (code "89") (name "unconnected-(U7-PA0-WKUP-Pad23)") (class "Default")
      (node (ref "U7") (pin "23") (pinfunction "PA0-WKUP_23") (pintype "passive"))
    )
    (net (code "90") (name "unconnected-(U7-PA1-Pad24)") (class "Default")
      (node (ref "U7") (pin "24") (pinfunction "PA1_24") (pintype "passive"))
    )
    (net (code "91") (name "unconnected-(U7-PA2{slash}TX2-Pad25)") (class "Default")
      (node (ref "U7") (pin "25") (pinfunction "PA2/TX2_25") (pintype "passive"))
    )
    (net (code "92") (name "unconnected-(U7-PB0-Pad35)") (class "Default")
      (node (ref "U7") (pin "35") (pinfunction "PB0_35") (pintype "passive"))
    )
    (net (code "93") (name "unconnected-(U7-PB8-Pad95)") (class "Default")
      (node (ref "U7") (pin "95") (pinfunction "PB8_95") (pintype "passive"))
    )
    (net (code "94") (name "unconnected-(U7-PB9-Pad96)") (class "Default")
      (node (ref "U7") (pin "96") (pinfunction "PB9_96") (pintype "passive"))
    )
    (net (code "95") (name "unconnected-(U7-PC0-Pad15)") (class "Default")
      (node (ref "U7") (pin "15") (pinfunction "PC0_15") (pintype "passive"))
    )
    (net (code "96") (name "unconnected-(U7-PC1-Pad16)") (class "Default")
      (node (ref "U7") (pin "16") (pinfunction "PC1_16") (pintype "passive"))
    )
    (net (code "97") (name "unconnected-(U7-PC2-Pad17)") (class "Default")
      (node (ref "U7") (pin "17") (pinfunction "PC2_17") (pintype "passive"))
    )
    (net (code "98") (name "unconnected-(U7-PC3-Pad18)") (class "Default")
      (node (ref "U7") (pin "18") (pinfunction "PC3_18") (pintype "passive"))
    )
    (net (code "99") (name "unconnected-(U7-PC13{slash}TAMPER_RTC-Pad7)") (class "Default")
      (node (ref "U7") (pin "7") (pinfunction "PC13/TAMPER_RTC_7") (pintype "passive"))
    )
    (net (code "100") (name "unconnected-(U7-PC14{slash}OSC32_IN-Pad8)") (class "Default")
      (node (ref "U7") (pin "8") (pinfunction "PC14/OSC32_IN_8") (pintype "passive"))
    )
    (net (code "101") (name "unconnected-(U7-PC15{slash}OSC32_OUT-Pad9)") (class "Default")
      (node (ref "U7") (pin "9") (pinfunction "PC15/OSC32_OUT_9") (pintype "passive"))
    )
    (net (code "102") (name "unconnected-(U7-SCL1{slash}PB6-Pad92)") (class "Default")
      (node (ref "U7") (pin "92") (pinfunction "SCL1/PB6_92") (pintype "passive"))
    )
    (net (code "103") (name "unconnected-(U7-SPI2_MISO{slash}PB14-Pad53)") (class "Default")
      (node (ref "U7") (pin "53") (pinfunction "SPI2_MISO/PB14_53") (pintype "passive"))
    )
    (net (code "104") (name "unconnected-(U7-SPI3_MISO{slash}PB4-Pad90)") (class "Default")
      (node (ref "U7") (pin "90") (pinfunction "SPI3_MISO/PB4_90") (pintype "passive"))
    )
    (net (code "105") (name "unconnected-(U7-SPI3_MOSI{slash}PB5-Pad91)") (class "Default")
      (node (ref "U7") (pin "91") (pinfunction "SPI3_MOSI/PB5_91") (pintype "passive"))
    )
    (net (code "106") (name "unconnected-(U7-SPI3_SCLK{slash}PB3-Pad89)") (class "Default")
      (node (ref "U7") (pin "89") (pinfunction "SPI3_SCLK/PB3_89") (pintype "passive"))
    )
  )
)
